# Diff-Single_converter.net
KiCad netlist of a schematic drawn in EAGLE
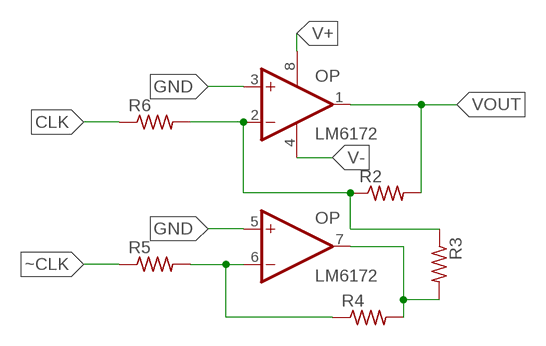
[diagram p0: schematic, sheet 1]

(export (version "E")
  (design (tool "Eeschema 10.0.6"))
  (components
    (comp (ref "OP")
      (value "LM6172")
      (footprint "eagle-import:SOIC127P599X175-8N")
      (libsource (lib "eagle-import") (part "LM6172"))
    )
    (comp (ref "R2")
      (value "R-US_R1206")
      (footprint "eagle-import:R1206")
      (libsource (lib "eagle-import") (part "R-US_R1206"))
    )
    (comp (ref "R3")
      (value "R-US_R1206")
      (footprint "eagle-import:R1206")
      (libsource (lib "eagle-import") (part "R-US_R1206"))
    )
    (comp (ref "R4")
      (value "R-US_R1206")
      (footprint "eagle-import:R1206")
      (libsource (lib "eagle-import") (part "R-US_R1206"))
    )
    (comp (ref "R5")
      (value "R-US_R1206")
      (footprint "eagle-import:R1206")
      (libsource (lib "eagle-import") (part "R-US_R1206"))
    )
    (comp (ref "R6")
      (value "R-US_R1206")
      (footprint "eagle-import:R1206")
      (libsource (lib "eagle-import") (part "R-US_R1206"))
    )
  )
  (nets
    (net (code "1") (name "/~{CLK}") (class "Default")
      (node (ref "R5") (pin "1") (pinfunction "1_1") (pintype "passive"))
    )
    (net (code "2") (name "CLK") (class "Default")
      (node (ref "R6") (pin "1") (pinfunction "1_1") (pintype "passive"))
    )
    (net (code "3") (name "GND") (class "Default")
      (node (ref "OP") (pin "3") (pinfunction "+IN_3") (pintype "input"))
      (node (ref "OP") (pin "5") (pinfunction "+IN1_5") (pintype "input"))
    )
    (net (code "4") (name "Net-(OP--IN)") (class "Default")
      (node (ref "OP") (pin "2") (pinfunction "-IN_2") (pintype "input"))
      (node (ref "R2") (pin "1") (pinfunction "1_1") (pintype "passive"))
      (node (ref "R3") (pin "1") (pinfunction "1_1") (pintype "passive"))
      (node (ref "R6") (pin "2") (pinfunction "2_2") (pintype "passive"))
    )
    (net (code "5") (name "Net-(OP--IN1)") (class "Default")
      (node (ref "OP") (pin "6") (pinfunction "-IN1_6") (pintype "input"))
      (node (ref "R4") (pin "1") (pinfunction "1_1") (pintype "passive"))
      (node (ref "R5") (pin "2") (pinfunction "2_2") (pintype "passive"))
    )
    (net (code "6") (name "Net-(OP-OUT1)") (class "Default")
      (node (ref "OP") (pin "7") (pinfunction "OUT1_7") (pintype "output"))
      (node (ref "R3") (pin "2") (pinfunction "2_2") (pintype "passive"))
      (node (ref "R4") (pin "2") (pinfunction "2_2") (pintype "passive"))
    )
    (net (code "7") (name "V+") (class "Default")
      (node (ref "OP") (pin "8") (pinfunction "V+_8") (pintype "power_in"))
    )
    (net (code "8") (name "V-") (class "Default")
      (node (ref "OP") (pin "4") (pinfunction "V-_4") (pintype "power_in"))
    )
    (net (code "9") (name "VOUT") (class "Default")
      (node (ref "OP") (pin "1") (pinfunction "OUT_1") (pintype "output"))
      (node (ref "R2") (pin "2") (pinfunction "2_2") (pintype "passive"))
    )
  )
)
